# USB_JTAG.net
KiCad netlist of a schematic drawn in Altium Designer
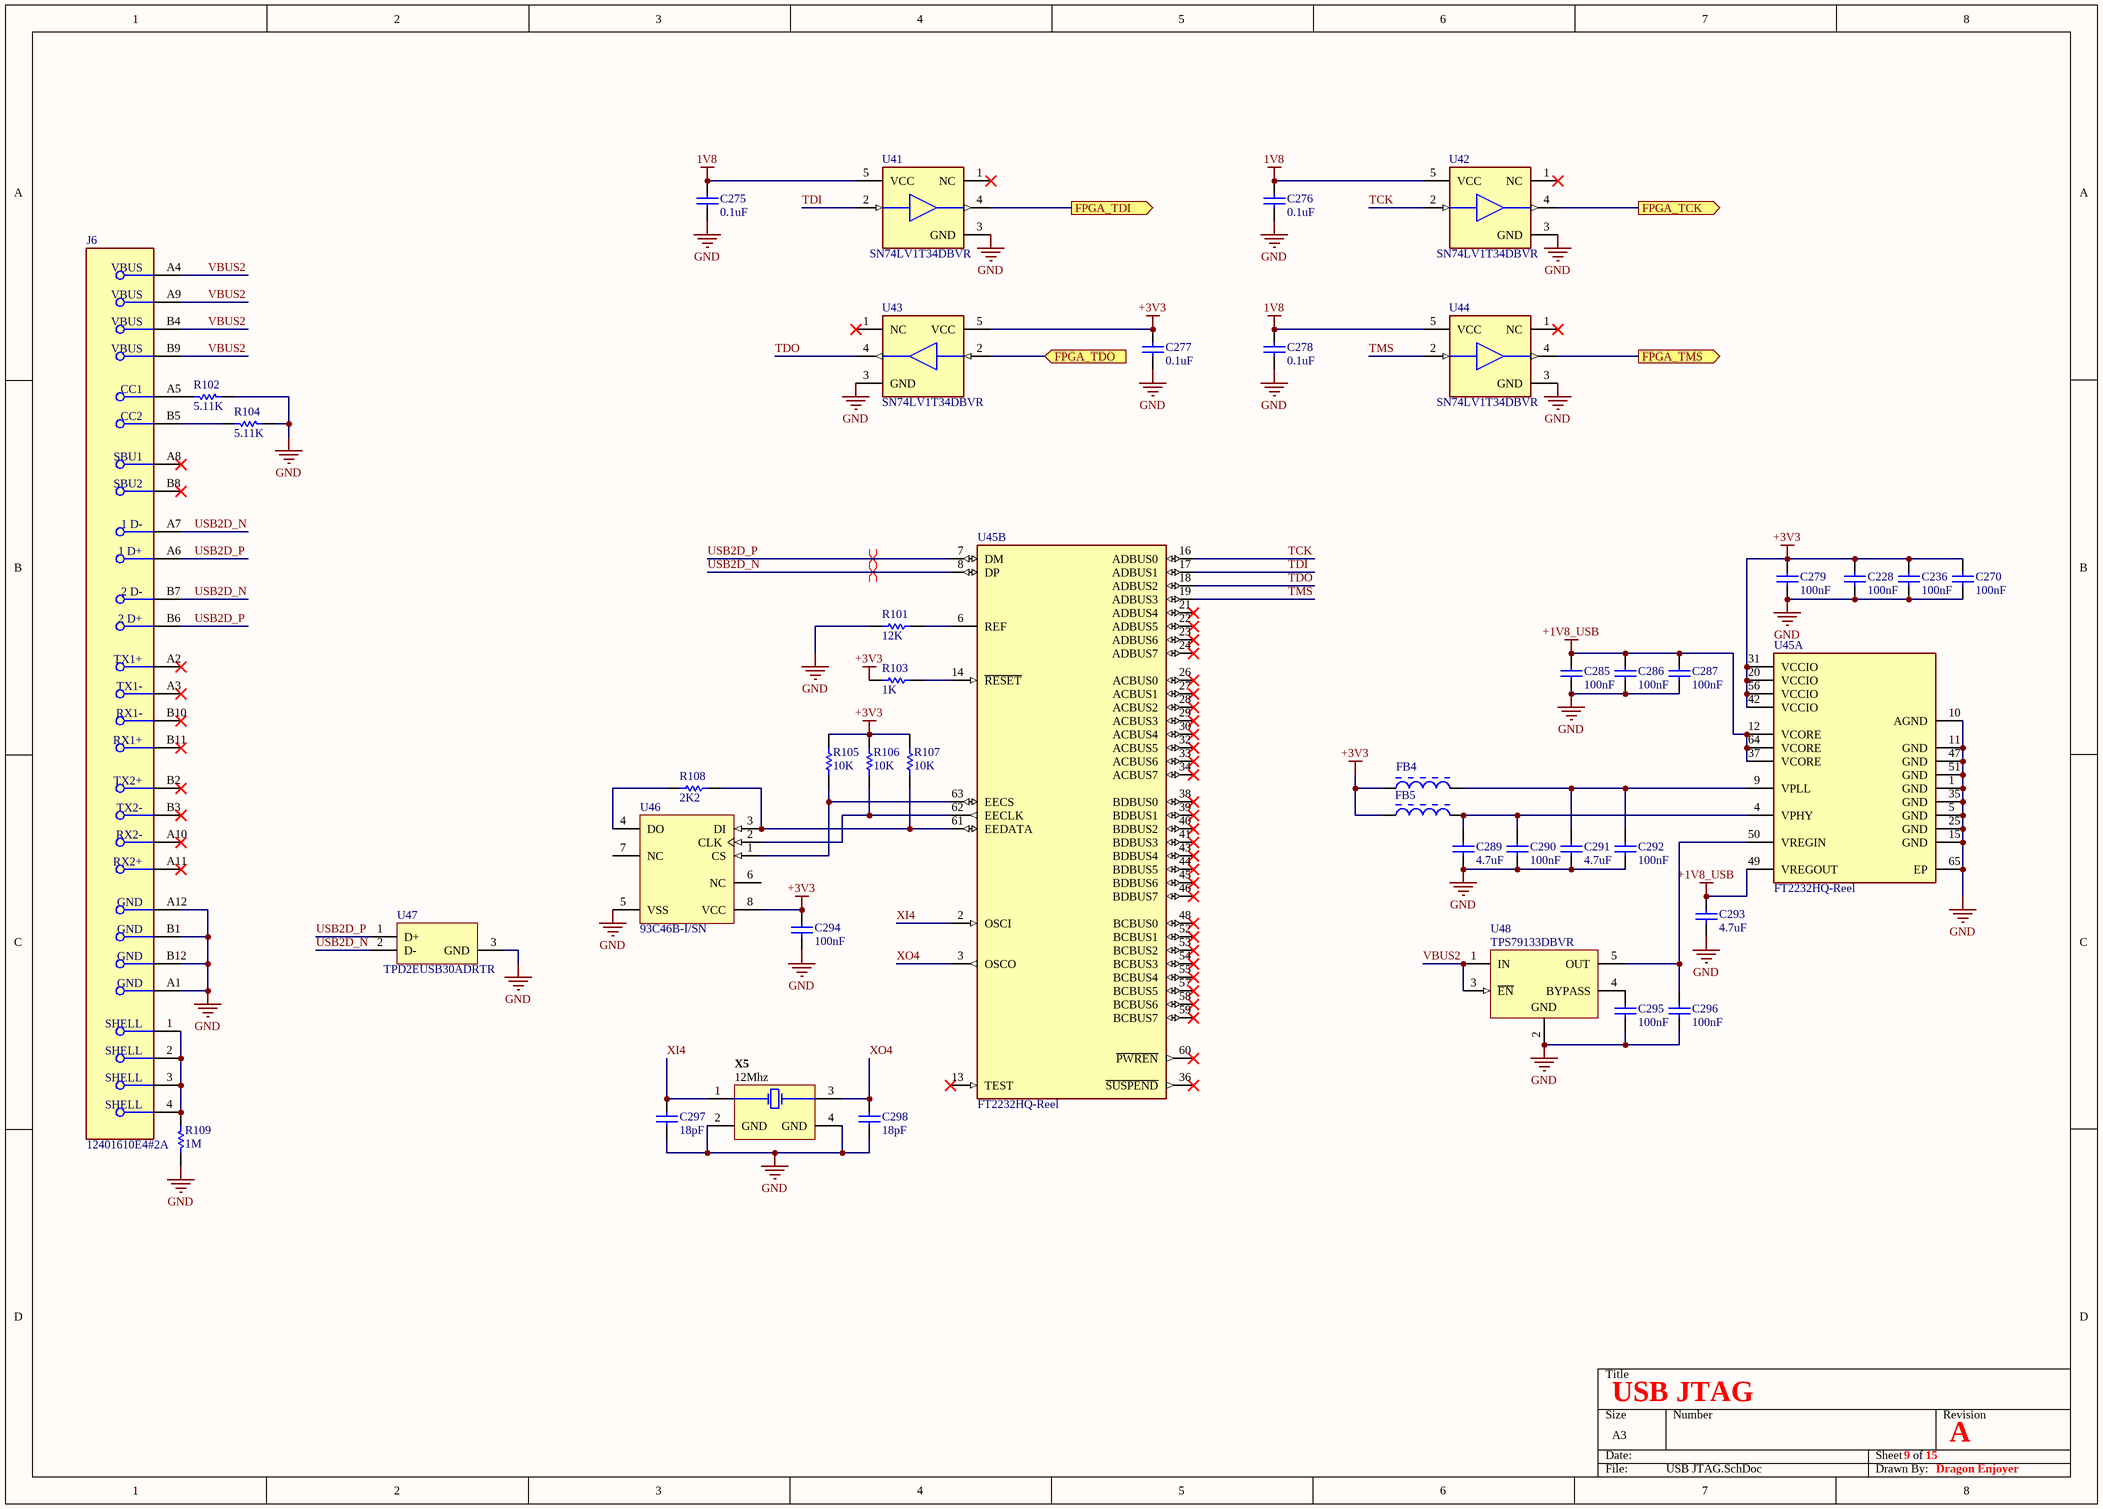
[diagram p0: USB JTAG.SchDoc]

(export (version "E")
  (design (tool "Eeschema 10.0.6"))
  (components
    (comp (ref "C228")
      (value "100nF")
      (footprint "CAPC0603X33X15LL03T05")
      (fields
        (field (name "PART NUMBER") "02016D104KAT2A")
        (field (name "MANUFACTURER") "AVX Interconnect / Elco")
      )
      (libsource (lib "Altium Content Vault") (part "CAP"))
    )
    (comp (ref "C236")
      (value "100nF")
      (footprint "CAPC0603X33X15LL03T05")
      (fields
        (field (name "PART NUMBER") "02016D104KAT2A")
        (field (name "MANUFACTURER") "AVX Interconnect / Elco")
      )
      (libsource (lib "Altium Content Vault") (part "CAP"))
    )
    (comp (ref "C270")
      (value "100nF")
      (footprint "CAPC0603X33X15LL03T05")
      (fields
        (field (name "PART NUMBER") "02016D104KAT2A")
        (field (name "MANUFACTURER") "AVX Interconnect / Elco")
      )
      (libsource (lib "Altium Content Vault") (part "CAP"))
    )
    (comp (ref "C275")
      (value "0.1uF")
      (footprint "CAPC1005X56X25LL10T15")
      (fields
        (field (name "MANUFACTURER") "AVX Interconnect / Elco")
        (field (name "PART NUMBER") "04026D104KAT2A")
      )
      (libsource (lib "Altium Content Vault") (part "CAP"))
    )
    (comp (ref "C276")
      (value "0.1uF")
      (footprint "CAPC1005X56X25LL10T15")
      (fields
        (field (name "MANUFACTURER") "AVX Interconnect / Elco")
        (field (name "PART NUMBER") "04026D104KAT2A")
      )
      (libsource (lib "Altium Content Vault") (part "CAP"))
    )
    (comp (ref "C277")
      (value "0.1uF")
      (footprint "CAPC1005X56X25LL10T15")
      (fields
        (field (name "MANUFACTURER") "AVX Interconnect / Elco")
        (field (name "PART NUMBER") "04026D104KAT2A")
      )
      (libsource (lib "Altium Content Vault") (part "CAP"))
    )
    (comp (ref "C278")
      (value "0.1uF")
      (footprint "CAPC1005X56X25LL10T15")
      (fields
        (field (name "MANUFACTURER") "AVX Interconnect / Elco")
        (field (name "PART NUMBER") "04026D104KAT2A")
      )
      (libsource (lib "Altium Content Vault") (part "CAP"))
    )
    (comp (ref "C279")
      (value "100nF")
      (footprint "CAPC0603X33X15LL03T05")
      (fields
        (field (name "PART NUMBER") "02016D104KAT2A")
        (field (name "MANUFACTURER") "AVX Interconnect / Elco")
      )
      (libsource (lib "Altium Content Vault") (part "CAP"))
    )
    (comp (ref "C285")
      (value "100nF")
      (footprint "CAPC0603X33X15LL03T05")
      (fields
        (field (name "PART NUMBER") "02016D104KAT2A")
        (field (name "MANUFACTURER") "AVX Interconnect / Elco")
      )
      (libsource (lib "Altium Content Vault") (part "CAP"))
    )
    (comp (ref "C286")
      (value "100nF")
      (footprint "CAPC0603X33X15LL03T05")
      (fields
        (field (name "PART NUMBER") "02016D104KAT2A")
        (field (name "MANUFACTURER") "AVX Interconnect / Elco")
      )
      (libsource (lib "Altium Content Vault") (part "CAP"))
    )
    (comp (ref "C287")
      (value "100nF")
      (footprint "CAPC0603X33X15LL03T05")
      (fields
        (field (name "PART NUMBER") "02016D104KAT2A")
        (field (name "MANUFACTURER") "AVX Interconnect / Elco")
      )
      (libsource (lib "Altium Content Vault") (part "CAP"))
    )
    (comp (ref "C289")
      (value "4.7uF")
      (footprint "CAPC1005X55X25LL05T10")
      (fields (field (name "PART NUMBER") "GRM155R60J475ME47D") (field (name "MANUFACTURER") "Murata"))
      (libsource (lib "Altium Content Vault") (part "CAP"))
    )
    (comp (ref "C290")
      (value "100nF")
      (footprint "CAPC0603X33X15LL03T05")
      (fields
        (field (name "PART NUMBER") "02016D104KAT2A")
        (field (name "MANUFACTURER") "AVX Interconnect / Elco")
      )
      (libsource (lib "Altium Content Vault") (part "CAP"))
    )
    (comp (ref "C291")
      (value "4.7uF")
      (footprint "CAPC1005X55X25LL05T10")
      (fields (field (name "PART NUMBER") "GRM155R60J475ME47D") (field (name "MANUFACTURER") "Murata"))
      (libsource (lib "Altium Content Vault") (part "CAP"))
    )
    (comp (ref "C292")
      (value "100nF")
      (footprint "CAPC0603X33X15LL03T05")
      (fields
        (field (name "PART NUMBER") "02016D104KAT2A")
        (field (name "MANUFACTURER") "AVX Interconnect / Elco")
      )
      (libsource (lib "Altium Content Vault") (part "CAP"))
    )
    (comp (ref "C293")
      (value "4.7uF")
      (footprint "CAPC1005X55X25LL05T10")
      (fields (field (name "PART NUMBER") "GRM155R60J475ME47D") (field (name "MANUFACTURER") "Murata"))
      (libsource (lib "Altium Content Vault") (part "CAP"))
    )
    (comp (ref "C294")
      (value "100nF")
      (footprint "CAPC0603X33X15ML03T05")
      (fields
        (field (name "PART NUMBER") "02016D104KAT2A")
        (field (name "MANUFACTURER") "AVX Interconnect / Elco")
      )
      (libsource (lib "Altium Content Vault") (part "CAP"))
    )
    (comp (ref "C295")
      (value "100nF")
      (footprint "CAPC0603X33X15LL03T05")
      (fields
        (field (name "PART NUMBER") "02016D104KAT2A")
        (field (name "MANUFACTURER") "AVX Interconnect / Elco")
      )
      (libsource (lib "Altium Content Vault") (part "CAP"))
    )
    (comp (ref "C296")
      (value "100nF")
      (footprint "CAPC0603X33X15LL03T05")
      (fields
        (field (name "PART NUMBER") "02016D104KAT2A")
        (field (name "MANUFACTURER") "AVX Interconnect / Elco")
      )
      (libsource (lib "Altium Content Vault") (part "CAP"))
    )
    (comp (ref "C297")
      (value "18pF")
      (footprint "CAPC1005X56X25ML10T15")
      (fields
        (field (name "PART NUMBER") "04025A180JAT2A")
        (field (name "MANUFACTURER") "AVX Interconnect / Elco")
      )
      (libsource (lib "Altium Content Vault") (part "CAP"))
    )
    (comp (ref "C298")
      (value "18pF")
      (footprint "CAPC1005X56X25ML10T15")
      (fields
        (field (name "PART NUMBER") "04025A180JAT2A")
        (field (name "MANUFACTURER") "AVX Interconnect / Elco")
      )
      (libsource (lib "Altium Content Vault") (part "CAP"))
    )
    (comp (ref "FB4")
      (value "BLM18PG121SN1D")
      (footprint "MURA-BLM18PG_KG-B25-CHIP-2_V1")
      (fields (field (name "MANUFACTURER") "Murata"))
      (libsource (lib "Altium Content Vault") (part "MURA-FB-2"))
    )
    (comp (ref "FB5")
      (value "BLM18PG121SN1D")
      (footprint "MURA-BLM18PG_KG-B25-CHIP-2_V1")
      (fields (field (name "MANUFACTURER") "Murata"))
      (libsource (lib "Altium Content Vault") (part "MURA-FB-2"))
    )
    (comp (ref "J6")
      (value "12401610E4#2A")
      (footprint "FP-12401610E4#2A-MFG")
      (description "CONN RCP USB3.1 TYPEC 24P SMD RA")
      (libsource (lib "Altium Content Vault") (part "7c76f4c47d7e2af8b8797da79635f2a"))
    )
    (comp (ref "R101")
      (value "12K")
      (footprint "RESC1005X40X25NL05T05")
      (fields (field (name "PART NUMBER") "CRCW040212K0FKED") (field (name "MANUFACTURER") "Vishay Dale"))
      (libsource (lib "Altium Content Vault") (part "RES"))
    )
    (comp (ref "R102")
      (value "5.11K")
      (footprint "RESC0603X28X15ML05T05")
      (fields (field (name "PART NUMBER") "CRCW02015K11FNED") (field (name "MANUFACTURER") "Vishay Dale"))
      (libsource (lib "Altium Content Vault") (part "RES"))
    )
    (comp (ref "R103")
      (value "1K")
      (footprint "RESC1005X40X25NL05T05")
      (fields (field (name "MANUFACTURER") "Vishay Dale") (field (name "PART NUMBER") "CRCW04021K00FKED"))
      (libsource (lib "Altium Content Vault") (part "RES"))
    )
    (comp (ref "R104")
      (value "5.11K")
      (footprint "RESC0603X28X15ML05T05")
      (fields (field (name "PART NUMBER") "CRCW02015K11FNED") (field (name "MANUFACTURER") "Vishay Dale"))
      (libsource (lib "Altium Content Vault") (part "RES"))
    )
    (comp (ref "R105")
      (value "10K")
      (footprint "RESC1005X40X25NL05T05")
      (fields (field (name "MANUFACTURER") "Vishay Dale") (field (name "PART NUMBER") "CRCW040210K0JNED"))
      (libsource (lib "Altium Content Vault") (part "RES"))
    )
    (comp (ref "R106")
      (value "10K")
      (footprint "RESC1005X40X25NL05T05")
      (fields (field (name "MANUFACTURER") "Vishay Dale") (field (name "PART NUMBER") "CRCW040210K0JNED"))
      (libsource (lib "Altium Content Vault") (part "RES"))
    )
    (comp (ref "R107")
      (value "10K")
      (footprint "RESC1005X40X25NL05T05")
      (fields (field (name "MANUFACTURER") "Vishay Dale") (field (name "PART NUMBER") "CRCW040210K0JNED"))
      (libsource (lib "Altium Content Vault") (part "RES"))
    )
    (comp (ref "R108")
      (value "2K2")
      (footprint "RESC1005X40X25NL05T05")
      (fields (field (name "PART NUMBER") "ERJ2RKF2201X") (field (name "MANUFACTURER") "Panasonic"))
      (libsource (lib "Altium Content Vault") (part "RES"))
    )
    (comp (ref "R109")
      (value "1M")
      (footprint "RESC1005X40X25ML05T05")
      (fields (field (name "MANUFACTURER") "Panasonic") (field (name "PART NUMBER") "ERJ-2GEJ105X"))
      (libsource (lib "Altium Content Vault") (part "RES"))
    )
    (comp (ref "U41")
      (value "SN74LV1T34DBVR")
      (footprint "FP-DBV0005A-IPC_B")
      (description "IC BUF NON-INVERT 5.5V SOT23-5")
      (libsource (lib "Altium Content Vault") (part "d03805866fcc65e5014dff611fc4129"))
    )
    (comp (ref "U42")
      (value "SN74LV1T34DBVR")
      (footprint "FP-DBV0005A-IPC_B")
      (description "IC BUF NON-INVERT 5.5V SOT23-5")
      (libsource (lib "Altium Content Vault") (part "d03805866fcc65e5014dff611fc4129"))
    )
    (comp (ref "U43")
      (value "SN74LV1T34DBVR")
      (footprint "FP-DBV0005A-IPC_B")
      (description "IC BUF NON-INVERT 5.5V SOT23-5")
      (libsource (lib "") (part "d03805866fcc65e5014dff611fc4129_1"))
    )
    (comp (ref "U44")
      (value "SN74LV1T34DBVR")
      (footprint "FP-DBV0005A-IPC_B")
      (description "IC BUF NON-INVERT 5.5V SOT23-5")
      (libsource (lib "Altium Content Vault") (part "d03805866fcc65e5014dff611fc4129"))
    )
    (comp (ref "U45")
      (value "FT2232HQ-Reel")
      (footprint "FP-FT2232HQ-Reel-MFG")
      (description "IC USB HS DUAL UART/FIFO 64-QFN")
      (fields
        (field (name "OCTOPART") "https://octopart.com/ft2232hq-reel-ftdi-19172126")
        (field (name "MANUFACTURER") "FTDI")
      )
      (libsource (lib "Altium Content Vault") (part "69ab9ac86b67af101dfdf5de5064102"))
    )
    (comp (ref "U46")
      (value "93C46B-I/SN")
      (footprint "SOIC-SN8_M")
      (description "1K, 64x16-bit, 5.0V Microwire Serial EEPROM, 8-Pin SOIC 150mil, Industrial Temperature")
      (libsource (lib "Altium Content Vault") (part "MEM-SEEPROM-93AA46B-P-8"))
    )
    (comp (ref "U47")
      (value "TPD2EUSB30ADRTR")
      (footprint "DRT0003A")
      (fields (field (name "MANUFACTURER") "Texas Instruments"))
      (libsource (lib "Altium Content Vault") (part "TI-TPD2EUSB30A-SOT_DRT-3"))
    )
    (comp (ref "U48")
      (value "TPS79133DBVR")
      (footprint "DBV0005A_N")
      (fields (field (name "MANUFACTURER") "Texas Instruments"))
      (libsource (lib "Altium Content Vault") (part "TI-TPS7XXXX-DBV5_A"))
    )
    (comp (ref "X5")
      (value "12Mhz")
      (footprint "ABRACON_ABM8G_V")
      (fields (field (name "TOLERANCE") "20PPM") (field (name "MANUFACTURER") "ABRACON"))
      (libsource (lib "Altium Content Vault") (part "XTAL-1-3-4"))
    )
  )
  (nets
    (net (code "1") (name "+1V8_USB") (class "Default")
      (node (ref "C285") (pin "2") (pinfunction "2_2") (pintype "passive"))
      (node (ref "C286") (pin "2") (pinfunction "2_2") (pintype "passive"))
      (node (ref "C287") (pin "2") (pinfunction "2_2") (pintype "passive"))
      (node (ref "C293") (pin "2") (pinfunction "2_2") (pintype "passive"))
      (node (ref "U45") (pin "12") (pinfunction "VCORE_12") (pintype "power_in"))
      (node (ref "U45") (pin "37") (pinfunction "VCORE_37") (pintype "power_in"))
      (node (ref "U45") (pin "49") (pinfunction "VREGOUT_49") (pintype "power_in"))
      (node (ref "U45") (pin "64") (pinfunction "VCORE_64") (pintype "power_in"))
    )
    (net (code "2") (name "+3V3") (class "Default")
      (node (ref "C228") (pin "2") (pinfunction "2_2") (pintype "passive"))
      (node (ref "C236") (pin "2") (pinfunction "2_2") (pintype "passive"))
      (node (ref "C270") (pin "2") (pinfunction "2_2") (pintype "passive"))
      (node (ref "C277") (pin "2") (pinfunction "2_2") (pintype "passive"))
      (node (ref "C279") (pin "2") (pinfunction "2_2") (pintype "passive"))
      (node (ref "C294") (pin "2") (pinfunction "2_2") (pintype "passive"))
      (node (ref "FB4") (pin "1") (pinfunction "1_1") (pintype "passive"))
      (node (ref "FB5") (pin "1") (pinfunction "1_1") (pintype "passive"))
      (node (ref "R103") (pin "1") (pinfunction "1_1") (pintype "passive"))
      (node (ref "R105") (pin "2") (pinfunction "2_2") (pintype "passive"))
      (node (ref "R106") (pin "2") (pinfunction "2_2") (pintype "passive"))
      (node (ref "R107") (pin "2") (pinfunction "2_2") (pintype "passive"))
      (node (ref "U43") (pin "5") (pinfunction "VCC_5") (pintype "power_in"))
      (node (ref "U45") (pin "20") (pinfunction "VCCIO_20") (pintype "power_in"))
      (node (ref "U45") (pin "31") (pinfunction "VCCIO_31") (pintype "power_in"))
      (node (ref "U45") (pin "42") (pinfunction "VCCIO_42") (pintype "power_in"))
      (node (ref "U45") (pin "56") (pinfunction "VCCIO_56") (pintype "power_in"))
      (node (ref "U46") (pin "8") (pinfunction "VCC_8") (pintype "power_in"))
    )
    (net (code "3") (name "/FPGA_TCK") (class "Default")
      (node (ref "U42") (pin "4") (pinfunction "Y_4") (pintype "output"))
    )
    (net (code "4") (name "/FPGA_TDI") (class "Default")
      (node (ref "U41") (pin "4") (pinfunction "Y_4") (pintype "output"))
    )
    (net (code "5") (name "/FPGA_TDO") (class "Default")
      (node (ref "U43") (pin "2") (pinfunction "A_2") (pintype "input"))
    )
    (net (code "6") (name "/FPGA_TMS") (class "Default")
      (node (ref "U44") (pin "4") (pinfunction "Y_4") (pintype "output"))
    )
    (net (code "7") (name "/TCK") (class "Default")
      (node (ref "U42") (pin "2") (pinfunction "A_2") (pintype "input"))
      (node (ref "U45") (pin "16") (pinfunction "ADBUS0_16") (pintype "bidirectional"))
    )
    (net (code "8") (name "/TDI") (class "Default")
      (node (ref "U41") (pin "2") (pinfunction "A_2") (pintype "input"))
      (node (ref "U45") (pin "17") (pinfunction "ADBUS1_17") (pintype "bidirectional"))
    )
    (net (code "9") (name "/TDO") (class "Default")
      (node (ref "U43") (pin "4") (pinfunction "Y_4") (pintype "output"))
      (node (ref "U45") (pin "18") (pinfunction "ADBUS2_18") (pintype "bidirectional"))
    )
    (net (code "10") (name "/TMS") (class "Default")
      (node (ref "U44") (pin "2") (pinfunction "A_2") (pintype "input"))
      (node (ref "U45") (pin "19") (pinfunction "ADBUS3_19") (pintype "bidirectional"))
    )
    (net (code "11") (name "/USB2D_N") (class "Default")
      (node (ref "J6") (pin "A7") (pinfunction "1_D-_A7") (pintype "passive"))
      (node (ref "J6") (pin "B7") (pinfunction "2_D-_B7") (pintype "passive"))
      (node (ref "U45") (pin "8") (pinfunction "DP_8") (pintype "bidirectional"))
      (node (ref "U47") (pin "2") (pinfunction "D-_2") (pintype "passive"))
    )
    (net (code "12") (name "/USB2D_P") (class "Default")
      (node (ref "J6") (pin "A6") (pinfunction "1_D+_A6") (pintype "passive"))
      (node (ref "J6") (pin "B6") (pinfunction "2_D+_B6") (pintype "passive"))
      (node (ref "U45") (pin "7") (pinfunction "DM_7") (pintype "bidirectional"))
      (node (ref "U47") (pin "1") (pinfunction "D+_1") (pintype "passive"))
    )
    (net (code "13") (name "/VBUS2") (class "Default")
      (node (ref "J6") (pin "A4") (pinfunction "VBUS_A4") (pintype "passive"))
      (node (ref "J6") (pin "A9") (pinfunction "VBUS_A9") (pintype "passive"))
      (node (ref "J6") (pin "B4") (pinfunction "VBUS_B4") (pintype "passive"))
      (node (ref "J6") (pin "B9") (pinfunction "VBUS_B9") (pintype "passive"))
      (node (ref "U48") (pin "1") (pinfunction "IN_1") (pintype "power_in"))
      (node (ref "U48") (pin "3") (pinfunction "~{EN}_3") (pintype "input"))
    )
    (net (code "14") (name "/XI4") (class "Default")
      (node (ref "C297") (pin "2") (pinfunction "2_2") (pintype "passive"))
      (node (ref "U45") (pin "2") (pinfunction "OSCI_2") (pintype "input"))
      (node (ref "X5") (pin "1") (pinfunction "X1_1") (pintype "passive"))
    )
    (net (code "15") (name "/XO4") (class "Default")
      (node (ref "C298") (pin "2") (pinfunction "2_2") (pintype "passive"))
      (node (ref "U45") (pin "3") (pinfunction "OSCO_3") (pintype "output"))
      (node (ref "X5") (pin "3") (pinfunction "X2_3") (pintype "passive"))
    )
    (net (code "16") (name "1V8") (class "Default")
      (node (ref "C275") (pin "2") (pinfunction "2_2") (pintype "passive"))
      (node (ref "C276") (pin "2") (pinfunction "2_2") (pintype "passive"))
      (node (ref "C278") (pin "2") (pinfunction "2_2") (pintype "passive"))
      (node (ref "U41") (pin "5") (pinfunction "VCC_5") (pintype "power_in"))
      (node (ref "U42") (pin "5") (pinfunction "VCC_5") (pintype "power_in"))
      (node (ref "U44") (pin "5") (pinfunction "VCC_5") (pintype "power_in"))
    )
    (net (code "17") (name "GND") (class "Default")
      (node (ref "C228") (pin "1") (pinfunction "1_1") (pintype "passive"))
      (node (ref "C236") (pin "1") (pinfunction "1_1") (pintype "passive"))
      (node (ref "C270") (pin "1") (pinfunction "1_1") (pintype "passive"))
      (node (ref "C275") (pin "1") (pinfunction "1_1") (pintype "passive"))
      (node (ref "C276") (pin "1") (pinfunction "1_1") (pintype "passive"))
      (node (ref "C277") (pin "1") (pinfunction "1_1") (pintype "passive"))
      (node (ref "C278") (pin "1") (pinfunction "1_1") (pintype "passive"))
      (node (ref "C279") (pin "1") (pinfunction "1_1") (pintype "passive"))
      (node (ref "C285") (pin "1") (pinfunction "1_1") (pintype "passive"))
      (node (ref "C286") (pin "1") (pinfunction "1_1") (pintype "passive"))
      (node (ref "C287") (pin "1") (pinfunction "1_1") (pintype "passive"))
      (node (ref "C289") (pin "1") (pinfunction "1_1") (pintype "passive"))
      (node (ref "C290") (pin "1") (pinfunction "1_1") (pintype "passive"))
      (node (ref "C291") (pin "1") (pinfunction "1_1") (pintype "passive"))
      (node (ref "C292") (pin "1") (pinfunction "1_1") (pintype "passive"))
      (node (ref "C293") (pin "1") (pinfunction "1_1") (pintype "passive"))
      (node (ref "C294") (pin "1") (pinfunction "1_1") (pintype "passive"))
      (node (ref "C295") (pin "1") (pinfunction "1_1") (pintype "passive"))
      (node (ref "C296") (pin "1") (pinfunction "1_1") (pintype "passive"))
      (node (ref "C297") (pin "1") (pinfunction "1_1") (pintype "passive"))
      (node (ref "C298") (pin "1") (pinfunction "1_1") (pintype "passive"))
      (node (ref "J6") (pin "A1") (pinfunction "GND_A1") (pintype "power_in"))
      (node (ref "J6") (pin "A12") (pinfunction "GND_A12") (pintype "power_in"))
      (node (ref "J6") (pin "B1") (pinfunction "GND_B1") (pintype "power_in"))
      (node (ref "J6") (pin "B12") (pinfunction "GND_B12") (pintype "power_in"))
      (node (ref "R101") (pin "1") (pinfunction "1_1") (pintype "passive"))
      (node (ref "R102") (pin "1") (pinfunction "1_1") (pintype "passive"))
      (node (ref "R104") (pin "1") (pinfunction "1_1") (pintype "passive"))
      (node (ref "R109") (pin "1") (pinfunction "1_1") (pintype "passive"))
      (node (ref "U41") (pin "3") (pinfunction "GND_3") (pintype "passive"))
      (node (ref "U42") (pin "3") (pinfunction "GND_3") (pintype "passive"))
      (node (ref "U43") (pin "3") (pinfunction "GND_3") (pintype "passive"))
      (node (ref "U44") (pin "3") (pinfunction "GND_3") (pintype "passive"))
      (node (ref "U45") (pin "1") (pinfunction "GND_1") (pintype "power_in"))
      (node (ref "U45") (pin "10") (pinfunction "AGND_10") (pintype "power_in"))
      (node (ref "U45") (pin "11") (pinfunction "GND_11") (pintype "power_in"))
      (node (ref "U45") (pin "15") (pinfunction "GND_15") (pintype "power_in"))
      (node (ref "U45") (pin "25") (pinfunction "GND_25") (pintype "power_in"))
      (node (ref "U45") (pin "35") (pinfunction "GND_35") (pintype "power_in"))
      (node (ref "U45") (pin "47") (pinfunction "GND_47") (pintype "power_in"))
      (node (ref "U45") (pin "5") (pinfunction "GND_5") (pintype "power_in"))
      (node (ref "U45") (pin "51") (pinfunction "GND_51") (pintype "power_in"))
      (node (ref "U45") (pin "65") (pinfunction "EP_65") (pintype "passive"))
      (node (ref "U46") (pin "5") (pinfunction "VSS_5") (pintype "passive"))
      (node (ref "U47") (pin "3") (pinfunction "GND_3") (pintype "passive"))
      (node (ref "U48") (pin "2") (pinfunction "GND_2") (pintype "passive"))
      (node (ref "X5") (pin "2") (pinfunction "GND_2") (pintype "passive"))
      (node (ref "X5") (pin "4") (pinfunction "GND_4") (pintype "passive"))
    )
    (net (code "18") (name "Net-(J6-CC1)") (class "Default")
      (node (ref "J6") (pin "A5") (pinfunction "CC1_A5") (pintype "passive"))
      (node (ref "R102") (pin "2") (pinfunction "2_2") (pintype "passive"))
    )
    (net (code "19") (name "Net-(J6-CC2)") (class "Default")
      (node (ref "J6") (pin "B5") (pinfunction "CC2_B5") (pintype "passive"))
      (node (ref "R104") (pin "2") (pinfunction "2_2") (pintype "passive"))
    )
    (net (code "20") (name "Net-(J6-SHELL-Pad1)") (class "Default")
      (node (ref "J6") (pin "1") (pinfunction "SHELL_1") (pintype "power_in"))
      (node (ref "J6") (pin "2") (pinfunction "SHELL_2") (pintype "power_in"))
      (node (ref "J6") (pin "3") (pinfunction "SHELL_3") (pintype "power_in"))
      (node (ref "J6") (pin "4") (pinfunction "SHELL_4") (pintype "power_in"))
      (node (ref "R109") (pin "2") (pinfunction "2_2") (pintype "passive"))
    )
    (net (code "21") (name "Net-(U45A-VPHY)") (class "Default")
      (node (ref "C289") (pin "2") (pinfunction "2_2") (pintype "passive"))
      (node (ref "C290") (pin "2") (pinfunction "2_2") (pintype "passive"))
      (node (ref "FB5") (pin "2") (pinfunction "2_2") (pintype "passive"))
      (node (ref "U45") (pin "4") (pinfunction "VPHY_4") (pintype "power_in"))
    )
    (net (code "22") (name "Net-(U45A-VPLL)") (class "Default")
      (node (ref "C291") (pin "2") (pinfunction "2_2") (pintype "passive"))
      (node (ref "C292") (pin "2") (pinfunction "2_2") (pintype "passive"))
      (node (ref "FB4") (pin "2") (pinfunction "2_2") (pintype "passive"))
      (node (ref "U45") (pin "9") (pinfunction "VPLL_9") (pintype "power_in"))
    )
    (net (code "23") (name "Net-(U45A-VREGIN)") (class "Default")
      (node (ref "C296") (pin "2") (pinfunction "2_2") (pintype "passive"))
      (node (ref "U45") (pin "50") (pinfunction "VREGIN_50") (pintype "power_in"))
      (node (ref "U48") (pin "5") (pinfunction "OUT_5") (pintype "power_in"))
    )
    (net (code "24") (name "Net-(U45B-EECLK)") (class "Default")
      (node (ref "R106") (pin "1") (pinfunction "1_1") (pintype "passive"))
      (node (ref "U45") (pin "62") (pinfunction "EECLK_62") (pintype "output"))
      (node (ref "U46") (pin "2") (pinfunction "CLK_2") (pintype "input"))
    )
    (net (code "25") (name "Net-(U45B-EECS)") (class "Default")
      (node (ref "R105") (pin "1") (pinfunction "1_1") (pintype "passive"))
      (node (ref "U45") (pin "63") (pinfunction "EECS_63") (pintype "bidirectional"))
      (node (ref "U46") (pin "1") (pinfunction "CS_1") (pintype "input"))
    )
    (net (code "26") (name "Net-(U45B-EEDATA)") (class "Default")
      (node (ref "R107") (pin "1") (pinfunction "1_1") (pintype "passive"))
      (node (ref "R108") (pin "2") (pinfunction "2_2") (pintype "passive"))
      (node (ref "U45") (pin "61") (pinfunction "EEDATA_61") (pintype "bidirectional"))
      (node (ref "U46") (pin "3") (pinfunction "DI_3") (pintype "input"))
    )
    (net (code "27") (name "Net-(U45B-REF)") (class "Default")
      (node (ref "R101") (pin "2") (pinfunction "2_2") (pintype "passive"))
      (node (ref "U45") (pin "6") (pinfunction "REF_6") (pintype "passive"))
    )
    (net (code "28") (name "Net-(U45B-~{RESET})") (class "Default")
      (node (ref "R103") (pin "2") (pinfunction "2_2") (pintype "passive"))
      (node (ref "U45") (pin "14") (pinfunction "~{RESET}_14") (pintype "input"))
    )
    (net (code "29") (name "Net-(U46-DO)") (class "Default")
      (node (ref "R108") (pin "1") (pinfunction "1_1") (pintype "passive"))
      (node (ref "U46") (pin "4") (pinfunction "DO_4") (pintype "tri_state"))
    )
    (net (code "30") (name "Net-(U48-BYPASS)") (class "Default")
      (node (ref "C295") (pin "2") (pinfunction "2_2") (pintype "passive"))
      (node (ref "U48") (pin "4") (pinfunction "BYPASS_4") (pintype "passive"))
    )
    (net (code "31") (name "unconnected-(J6-RX1+-PadB11)") (class "Default")
      (node (ref "J6") (pin "B11") (pinfunction "RX1+_B11") (pintype "passive+no_connect"))
    )
    (net (code "32") (name "unconnected-(J6-RX1--PadB10)") (class "Default")
      (node (ref "J6") (pin "B10") (pinfunction "RX1-_B10") (pintype "passive+no_connect"))
    )
    (net (code "33") (name "unconnected-(J6-RX2+-PadA11)") (class "Default")
      (node (ref "J6") (pin "A11") (pinfunction "RX2+_A11") (pintype "passive+no_connect"))
    )
    (net (code "34") (name "unconnected-(J6-RX2--PadA10)") (class "Default")
      (node (ref "J6") (pin "A10") (pinfunction "RX2-_A10") (pintype "passive+no_connect"))
    )
    (net (code "35") (name "unconnected-(J6-SBU1-PadA8)") (class "Default")
      (node (ref "J6") (pin "A8") (pinfunction "SBU1_A8") (pintype "passive+no_connect"))
    )
    (net (code "36") (name "unconnected-(J6-SBU2-PadB8)") (class "Default")
      (node (ref "J6") (pin "B8") (pinfunction "SBU2_B8") (pintype "passive+no_connect"))
    )
    (net (code "37") (name "unconnected-(J6-TX1+-PadA2)") (class "Default")
      (node (ref "J6") (pin "A2") (pinfunction "TX1+_A2") (pintype "passive+no_connect"))
    )
    (net (code "38") (name "unconnected-(J6-TX1--PadA3)") (class "Default")
      (node (ref "J6") (pin "A3") (pinfunction "TX1-_A3") (pintype "passive+no_connect"))
    )
    (net (code "39") (name "unconnected-(J6-TX2+-PadB2)") (class "Default")
      (node (ref "J6") (pin "B2") (pinfunction "TX2+_B2") (pintype "passive+no_connect"))
    )
    (net (code "40") (name "unconnected-(J6-TX2--PadB3)") (class "Default")
      (node (ref "J6") (pin "B3") (pinfunction "TX2-_B3") (pintype "passive+no_connect"))
    )
    (net (code "41") (name "unconnected-(U41-NC-Pad1)") (class "Default")
      (node (ref "U41") (pin "1") (pinfunction "NC_1") (pintype "passive+no_connect"))
    )
    (net (code "42") (name "unconnected-(U42-NC-Pad1)") (class "Default")
      (node (ref "U42") (pin "1") (pinfunction "NC_1") (pintype "passive+no_connect"))
    )
    (net (code "43") (name "unconnected-(U43-NC-Pad1)") (class "Default")
      (node (ref "U43") (pin "1") (pinfunction "NC_1") (pintype "passive+no_connect"))
    )
    (net (code "44") (name "unconnected-(U44-NC-Pad1)") (class "Default")
      (node (ref "U44") (pin "1") (pinfunction "NC_1") (pintype "passive+no_connect"))
    )
    (net (code "45") (name "unconnected-(U45B-ACBUS0-Pad26)") (class "Default")
      (node (ref "U45") (pin "26") (pinfunction "ACBUS0_26") (pintype "bidirectional+no_connect"))
    )
    (net (code "46") (name "unconnected-(U45B-ACBUS1-Pad27)") (class "Default")
      (node (ref "U45") (pin "27") (pinfunction "ACBUS1_27") (pintype "bidirectional+no_connect"))
    )
    (net (code "47") (name "unconnected-(U45B-ACBUS2-Pad28)") (class "Default")
      (node (ref "U45") (pin "28") (pinfunction "ACBUS2_28") (pintype "bidirectional+no_connect"))
    )
    (net (code "48") (name "unconnected-(U45B-ACBUS3-Pad29)") (class "Default")
      (node (ref "U45") (pin "29") (pinfunction "ACBUS3_29") (pintype "bidirectional+no_connect"))
    )
    (net (code "49") (name "unconnected-(U45B-ACBUS4-Pad30)") (class "Default")
      (node (ref "U45") (pin "30") (pinfunction "ACBUS4_30") (pintype "bidirectional+no_connect"))
    )
    (net (code "50") (name "unconnected-(U45B-ACBUS5-Pad32)") (class "Default")
      (node (ref "U45") (pin "32") (pinfunction "ACBUS5_32") (pintype "bidirectional+no_connect"))
    )
    (net (code "51") (name "unconnected-(U45B-ACBUS6-Pad33)") (class "Default")
      (node (ref "U45") (pin "33") (pinfunction "ACBUS6_33") (pintype "bidirectional+no_connect"))
    )
    (net (code "52") (name "unconnected-(U45B-ACBUS7-Pad34)") (class "Default")
      (node (ref "U45") (pin "34") (pinfunction "ACBUS7_34") (pintype "bidirectional+no_connect"))
    )
    (net (code "53") (name "unconnected-(U45B-ADBUS4-Pad21)") (class "Default")
      (node (ref "U45") (pin "21") (pinfunction "ADBUS4_21") (pintype "bidirectional+no_connect"))
    )
    (net (code "54") (name "unconnected-(U45B-ADBUS5-Pad22)") (class "Default")
      (node (ref "U45") (pin "22") (pinfunction "ADBUS5_22") (pintype "bidirectional+no_connect"))
    )
    (net (code "55") (name "unconnected-(U45B-ADBUS6-Pad23)") (class "Default")
      (node (ref "U45") (pin "23") (pinfunction "ADBUS6_23") (pintype "bidirectional+no_connect"))
    )
    (net (code "56") (name "unconnected-(U45B-ADBUS7-Pad24)") (class "Default")
      (node (ref "U45") (pin "24") (pinfunction "ADBUS7_24") (pintype "bidirectional+no_connect"))
    )
    (net (code "57") (name "unconnected-(U45B-BCBUS0-Pad48)") (class "Default")
      (node (ref "U45") (pin "48") (pinfunction "BCBUS0_48") (pintype "bidirectional+no_connect"))
    )
    (net (code "58") (name "unconnected-(U45B-BCBUS1-Pad52)") (class "Default")
      (node (ref "U45") (pin "52") (pinfunction "BCBUS1_52") (pintype "bidirectional+no_connect"))
    )
    (net (code "59") (name "unconnected-(U45B-BCBUS2-Pad53)") (class "Default")
      (node (ref "U45") (pin "53") (pinfunction "BCBUS2_53") (pintype "bidirectional+no_connect"))
    )
    (net (code "60") (name "unconnected-(U45B-BCBUS3-Pad54)") (class "Default")
      (node (ref "U45") (pin "54") (pinfunction "BCBUS3_54") (pintype "bidirectional+no_connect"))
    )
    (net (code "61") (name "unconnected-(U45B-BCBUS4-Pad55)") (class "Default")
      (node (ref "U45") (pin "55") (pinfunction "BCBUS4_55") (pintype "bidirectional+no_connect"))
    )
    (net (code "62") (name "unconnected-(U45B-BCBUS5-Pad57)") (class "Default")
      (node (ref "U45") (pin "57") (pinfunction "BCBUS5_57") (pintype "bidirectional+no_connect"))
    )
    (net (code "63") (name "unconnected-(U45B-BCBUS6-Pad58)") (class "Default")
      (node (ref "U45") (pin "58") (pinfunction "BCBUS6_58") (pintype "bidirectional+no_connect"))
    )
    (net (code "64") (name "unconnected-(U45B-BCBUS7-Pad59)") (class "Default")
      (node (ref "U45") (pin "59") (pinfunction "BCBUS7_59") (pintype "bidirectional+no_connect"))
    )
    (net (code "65") (name "unconnected-(U45B-BDBUS0-Pad38)") (class "Default")
      (node (ref "U45") (pin "38") (pinfunction "BDBUS0_38") (pintype "bidirectional+no_connect"))
    )
    (net (code "66") (name "unconnected-(U45B-BDBUS1-Pad39)") (class "Default")
      (node (ref "U45") (pin "39") (pinfunction "BDBUS1_39") (pintype "bidirectional+no_connect"))
    )
    (net (code "67") (name "unconnected-(U45B-BDBUS2-Pad40)") (class "Default")
      (node (ref "U45") (pin "40") (pinfunction "BDBUS2_40") (pintype "bidirectional+no_connect"))
    )
    (net (code "68") (name "unconnected-(U45B-BDBUS3-Pad41)") (class "Default")
      (node (ref "U45") (pin "41") (pinfunction "BDBUS3_41") (pintype "bidirectional+no_connect"))
    )
    (net (code "69") (name "unconnected-(U45B-BDBUS4-Pad43)") (class "Default")
      (node (ref "U45") (pin "43") (pinfunction "BDBUS4_43") (pintype "bidirectional+no_connect"))
    )
    (net (code "70") (name "unconnected-(U45B-BDBUS5-Pad44)") (class "Default")
      (node (ref "U45") (pin "44") (pinfunction "BDBUS5_44") (pintype "bidirectional+no_connect"))
    )
    (net (code "71") (name "unconnected-(U45B-BDBUS6-Pad45)") (class "Default")
      (node (ref "U45") (pin "45") (pinfunction "BDBUS6_45") (pintype "bidirectional+no_connect"))
    )
    (net (code "72") (name "unconnected-(U45B-BDBUS7-Pad46)") (class "Default")
      (node (ref "U45") (pin "46") (pinfunction "BDBUS7_46") (pintype "bidirectional+no_connect"))
    )
    (net (code "73") (name "unconnected-(U45B-TEST-Pad13)") (class "Default")
      (node (ref "U45") (pin "13") (pinfunction "TEST_13") (pintype "input+no_connect"))
    )
    (net (code "74") (name "unconnected-(U45B-~{PWREN}-Pad60)") (class "Default")
      (node (ref "U45") (pin "60") (pinfunction "~{PWREN}_60") (pintype "output+no_connect"))
    )
    (net (code "75") (name "unconnected-(U45B-~{SUSPEND}-Pad36)") (class "Default")
      (node (ref "U45") (pin "36") (pinfunction "~{SUSPEND}_36") (pintype "output+no_connect"))
    )
    (net (code "76") (name "unconnected-(U46-NC-Pad6)") (class "Default")
      (node (ref "U46") (pin "6") (pinfunction "NC_6") (pintype "passive"))
    )
    (net (code "77") (name "unconnected-(U46-NC-Pad7)") (class "Default")
      (node (ref "U46") (pin "7") (pinfunction "NC_7") (pintype "passive"))
    )
  )
)
